# reflow-arduino-controller.net
KiCad netlist of a schematic drawn in EAGLE
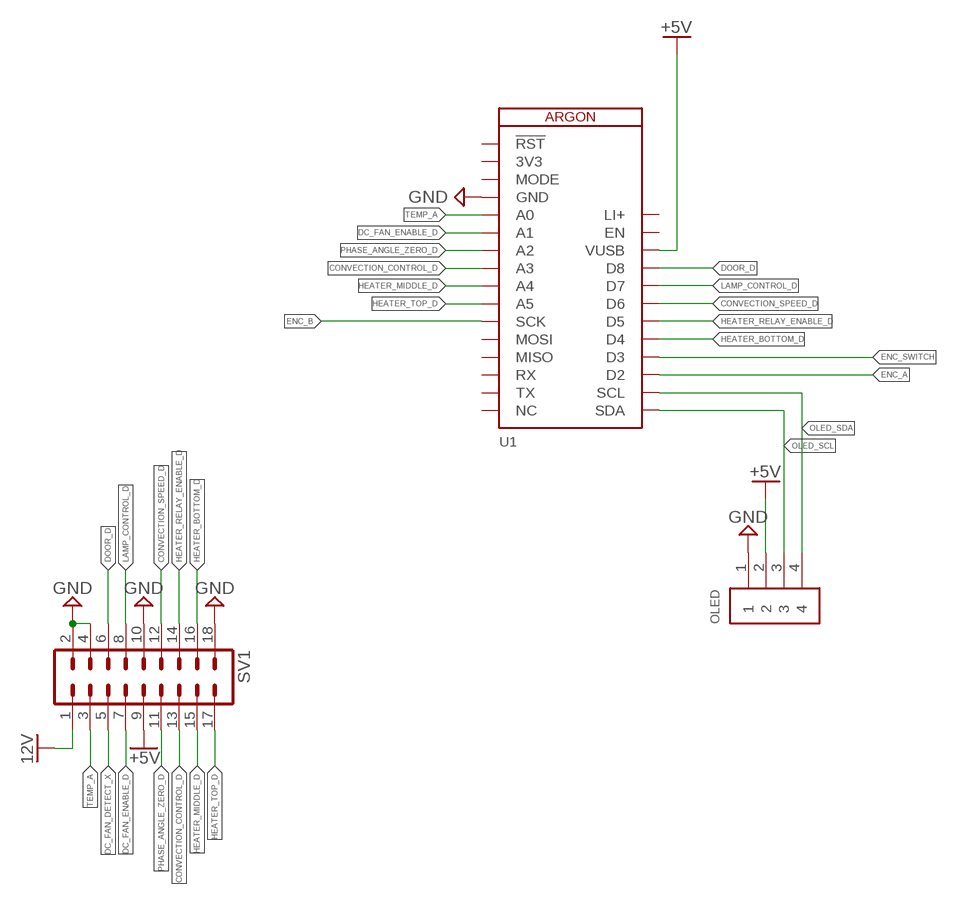
[diagram p0: schematic, sheet 1]

(export (version "E")
  (design (tool "Eeschema 10.0.6"))
  (components
    (comp (ref "OLED")
      (value "61300411121")
      (footprint "eagle-import:61300411121")
      (fields
        (field (name "DIGI_KEY_PART_NUMBER") "732-5317-ND")
        (field (name "MANUFACTURER") "Wurth Electronics Inc.")
        (field (name "CREATED_BY") "PCBLayout.com")
      )
      (libsource (lib "eagle-import") (part "61300411121"))
    )
    (comp (ref "SV1")
      (value "MA09-2")
      (footprint "eagle-import:MA09-2")
      (libsource (lib "eagle-import") (part "MA09-2"))
    )
    (comp (ref "U1")
      (value "ARGON")
      (footprint "eagle-import:ARGON")
      (libsource (lib "eagle-import") (part "ARGON"))
    )
  )
  (nets
    (net (code "1") (name "+5V") (class "Default")
      (node (ref "OLED") (pin "2") (pinfunction "2_2") (pintype "passive"))
      (node (ref "SV1") (pin "9") (pinfunction "9_9") (pintype "passive"))
      (node (ref "U1") (pin "26") (pinfunction "VUSB_26") (pintype "power_in"))
    )
    (net (code "2") (name "/3V3") (class "Default")
      (node (ref "U1") (pin "2") (pinfunction "3V3_2") (pintype "power_in"))
    )
    (net (code "3") (name "/LI+") (class "Default")
      (node (ref "U1") (pin "28") (pinfunction "LI+_28") (pintype "power_in"))
    )
    (net (code "4") (name "12V") (class "Default")
      (node (ref "SV1") (pin "1") (pinfunction "1_1") (pintype "passive"))
    )
    (net (code "5") (name "CONVECTION_CONTROL_D") (class "Default")
      (node (ref "SV1") (pin "13") (pinfunction "13_13") (pintype "passive"))
      (node (ref "U1") (pin "8") (pinfunction "A3_8") (pintype "bidirectional"))
    )
    (net (code "6") (name "CONVECTION_SPEED_D") (class "Default")
      (node (ref "SV1") (pin "12") (pinfunction "12_12") (pintype "passive"))
      (node (ref "U1") (pin "23") (pinfunction "D6_23") (pintype "bidirectional"))
    )
    (net (code "7") (name "DC_FAN_DETECT_X") (class "Default")
      (node (ref "SV1") (pin "5") (pinfunction "5_5") (pintype "passive"))
    )
    (net (code "8") (name "DC_FAN_ENABLE_D") (class "Default")
      (node (ref "SV1") (pin "7") (pinfunction "7_7") (pintype "passive"))
      (node (ref "U1") (pin "6") (pinfunction "A1_6") (pintype "bidirectional"))
    )
    (net (code "9") (name "DOOR_D") (class "Default")
      (node (ref "SV1") (pin "6") (pinfunction "6_6") (pintype "passive"))
      (node (ref "U1") (pin "25") (pinfunction "D8_25") (pintype "bidirectional"))
    )
    (net (code "10") (name "ENC_A") (class "Default")
      (node (ref "U1") (pin "19") (pinfunction "D2_19") (pintype "bidirectional"))
    )
    (net (code "11") (name "ENC_B") (class "Default")
      (node (ref "U1") (pin "11") (pinfunction "SCK_11") (pintype "bidirectional"))
    )
    (net (code "12") (name "ENC_SWITCH") (class "Default")
      (node (ref "U1") (pin "20") (pinfunction "D3_20") (pintype "bidirectional"))
    )
    (net (code "13") (name "GND") (class "Default")
      (node (ref "OLED") (pin "1") (pinfunction "1_1") (pintype "passive"))
      (node (ref "SV1") (pin "10") (pinfunction "10_10") (pintype "passive"))
      (node (ref "SV1") (pin "18") (pinfunction "18_18") (pintype "passive"))
      (node (ref "SV1") (pin "2") (pinfunction "2_2") (pintype "passive"))
      (node (ref "SV1") (pin "4") (pinfunction "4_4") (pintype "passive"))
      (node (ref "U1") (pin "4") (pinfunction "GND_4") (pintype "power_in"))
    )
    (net (code "14") (name "HEATER_BOTTOM_D") (class "Default")
      (node (ref "SV1") (pin "16") (pinfunction "16_16") (pintype "passive"))
      (node (ref "U1") (pin "21") (pinfunction "D4_21") (pintype "bidirectional"))
    )
    (net (code "15") (name "HEATER_MIDDLE_D") (class "Default")
      (node (ref "SV1") (pin "15") (pinfunction "15_15") (pintype "passive"))
      (node (ref "U1") (pin "9") (pinfunction "A4_9") (pintype "bidirectional"))
    )
    (net (code "16") (name "HEATER_RELAY_ENABLE_D") (class "Default")
      (node (ref "SV1") (pin "14") (pinfunction "14_14") (pintype "passive"))
      (node (ref "U1") (pin "22") (pinfunction "D5_22") (pintype "bidirectional"))
    )
    (net (code "17") (name "HEATER_TOP_D") (class "Default")
      (node (ref "SV1") (pin "17") (pinfunction "17_17") (pintype "passive"))
      (node (ref "U1") (pin "10") (pinfunction "A5_10") (pintype "bidirectional"))
    )
    (net (code "18") (name "LAMP_CONTROL_D") (class "Default")
      (node (ref "SV1") (pin "8") (pinfunction "8_8") (pintype "passive"))
      (node (ref "U1") (pin "24") (pinfunction "D7_24") (pintype "bidirectional"))
    )
    (net (code "19") (name "OLED_SCL") (class "Default")
      (node (ref "OLED") (pin "3") (pinfunction "3_3") (pintype "passive"))
      (node (ref "U1") (pin "17") (pinfunction "SDA_17") (pintype "bidirectional"))
    )
    (net (code "20") (name "OLED_SDA") (class "Default")
      (node (ref "OLED") (pin "4") (pinfunction "4_4") (pintype "passive"))
      (node (ref "U1") (pin "18") (pinfunction "SCL_18") (pintype "bidirectional"))
    )
    (net (code "21") (name "PHASE_ANGLE_ZERO_D") (class "Default")
      (node (ref "SV1") (pin "11") (pinfunction "11_11") (pintype "passive"))
      (node (ref "U1") (pin "7") (pinfunction "A2_7") (pintype "bidirectional"))
    )
    (net (code "22") (name "TEMP_A") (class "Default")
      (node (ref "SV1") (pin "3") (pinfunction "3_3") (pintype "passive"))
      (node (ref "U1") (pin "5") (pinfunction "A0_5") (pintype "bidirectional"))
    )
    (net (code "23") (name "unconnected-(U1-EN-Pad27)") (class "Default")
      (node (ref "U1") (pin "27") (pinfunction "EN_27") (pintype "input"))
    )
    (net (code "24") (name "unconnected-(U1-MISO-Pad13)") (class "Default")
      (node (ref "U1") (pin "13") (pinfunction "MISO_13") (pintype "bidirectional"))
    )
    (net (code "25") (name "unconnected-(U1-MODE-Pad3)") (class "Default")
      (node (ref "U1") (pin "3") (pinfunction "MODE_3") (pintype "bidirectional"))
    )
    (net (code "26") (name "unconnected-(U1-MOSI-Pad12)") (class "Default")
      (node (ref "U1") (pin "12") (pinfunction "MOSI_12") (pintype "bidirectional"))
    )
    (net (code "27") (name "unconnected-(U1-NC-Pad16)") (class "Default")
      (node (ref "U1") (pin "16") (pinfunction "NC_16") (pintype "bidirectional"))
    )
    (net (code "28") (name "unconnected-(U1-RX-Pad14)") (class "Default")
      (node (ref "U1") (pin "14") (pinfunction "RX_14") (pintype "bidirectional"))
    )
    (net (code "29") (name "unconnected-(U1-TX-Pad15)") (class "Default")
      (node (ref "U1") (pin "15") (pinfunction "TX_15") (pintype "bidirectional"))
    )
    (net (code "30") (name "unconnected-(U1-~{RST}-Pad1)") (class "Default")
      (node (ref "U1") (pin "1") (pinfunction "~{RST}_1") (pintype "input"))
    )
  )
)
